# LMH6881-Breakout.net
KiCad netlist of a schematic drawn in EAGLE
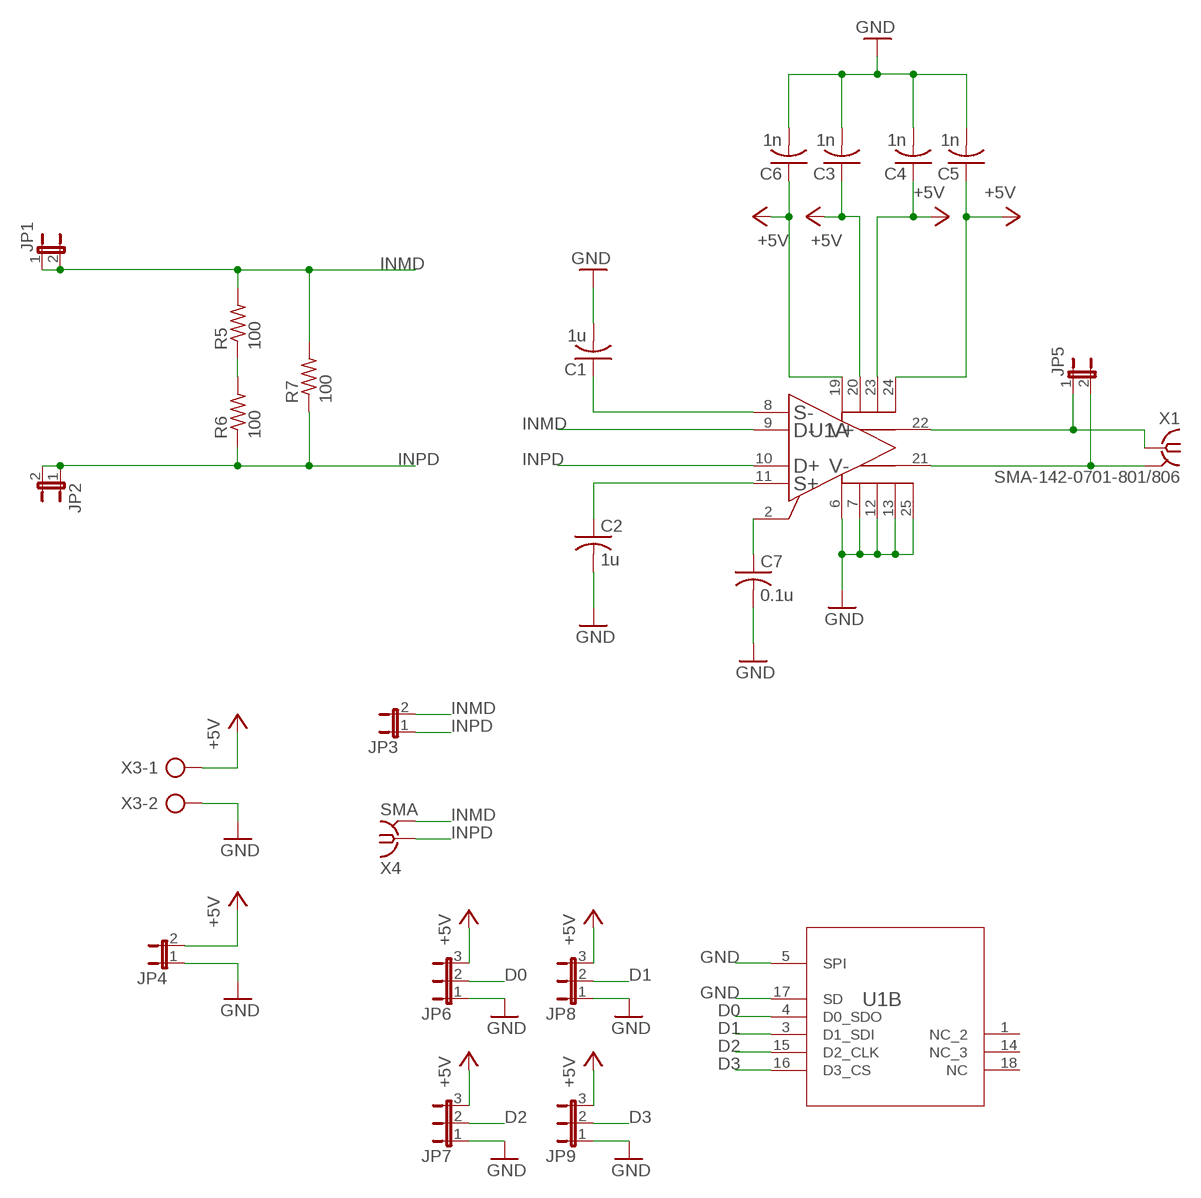
[diagram p0: schematic, sheet 1]

(export (version "E")
  (design (tool "Eeschema 10.0.6"))
  (components
    (comp (ref "C1")
      (value "1u")
      (footprint "eagle-import:C0805")
      (libsource (lib "eagle-import") (part "C-USC0805"))
    )
    (comp (ref "C2")
      (value "1u")
      (footprint "eagle-import:C0805")
      (libsource (lib "eagle-import") (part "C-USC0805"))
    )
    (comp (ref "C3")
      (value "1n")
      (footprint "eagle-import:C0805")
      (libsource (lib "eagle-import") (part "C-USC0805"))
    )
    (comp (ref "C4")
      (value "1n")
      (footprint "eagle-import:C0805")
      (libsource (lib "eagle-import") (part "C-USC0805"))
    )
    (comp (ref "C5")
      (value "1n")
      (footprint "eagle-import:C0805")
      (libsource (lib "eagle-import") (part "C-USC0805"))
    )
    (comp (ref "C6")
      (value "1n")
      (footprint "eagle-import:C0805")
      (libsource (lib "eagle-import") (part "C-USC0805"))
    )
    (comp (ref "C7")
      (value "0.1u")
      (footprint "eagle-import:C0805")
      (libsource (lib "eagle-import") (part "C-USC0805"))
    )
    (comp (ref "JP1")
      (value "JP1E")
      (footprint "eagle-import:JP1")
      (libsource (lib "eagle-import") (part "JP1E"))
    )
    (comp (ref "JP2")
      (value "JP1E")
      (footprint "eagle-import:JP1")
      (libsource (lib "eagle-import") (part "JP1E"))
    )
    (comp (ref "JP3")
      (value "JP1E")
      (footprint "eagle-import:JP1")
      (libsource (lib "eagle-import") (part "JP1E"))
    )
    (comp (ref "JP4")
      (value "JP1E")
      (footprint "eagle-import:JP1")
      (libsource (lib "eagle-import") (part "JP1E"))
    )
    (comp (ref "JP5")
      (value "JP1E")
      (footprint "eagle-import:JP1")
      (libsource (lib "eagle-import") (part "JP1E"))
    )
    (comp (ref "JP6")
      (value "JP2E")
      (footprint "eagle-import:JP2")
      (libsource (lib "eagle-import") (part "JP2E"))
    )
    (comp (ref "JP7")
      (value "JP2E")
      (footprint "eagle-import:JP2")
      (libsource (lib "eagle-import") (part "JP2E"))
    )
    (comp (ref "JP8")
      (value "JP2E")
      (footprint "eagle-import:JP2")
      (libsource (lib "eagle-import") (part "JP2E"))
    )
    (comp (ref "JP9")
      (value "JP2E")
      (footprint "eagle-import:JP2")
      (libsource (lib "eagle-import") (part "JP2E"))
    )
    (comp (ref "R5")
      (value "100")
      (footprint "eagle-import:R0805")
      (libsource (lib "eagle-import") (part "R-US_R0805"))
    )
    (comp (ref "R6")
      (value "100")
      (footprint "eagle-import:R0805")
      (libsource (lib "eagle-import") (part "R-US_R0805"))
    )
    (comp (ref "R7")
      (value "100")
      (footprint "eagle-import:R0805")
      (libsource (lib "eagle-import") (part "R-US_R0805"))
    )
    (comp (ref "U1")
      (value "LMH6881SQX/NOPB")
      (footprint "eagle-import:RTW0024A")
      (fields
        (field (name "ALTERNATEPARTNUMBER") "LMH6881SQNOPB")
        (field (name "MANUFACTURER") "Texas Instruments")
        (field (name "PARTNUMBER") "LMH6881SQXNOPB")
      )
      (libsource (lib "eagle-import") (part "LMH6881SQX/NOPB"))
    )
    (comp (ref "X1")
      (value "SMA-142-0701-801/806")
      (footprint "eagle-import:J502-ND-142-0701-801_806")
      (fields (field (name "MF") "JOHNSON COMPONENTS") (field (name "MPN") "142-0701-801"))
      (libsource (lib "eagle-import") (part "SMA-142-0701-801/806"))
    )
    (comp (ref "X3")
      (value "AK500/2")
      (footprint "eagle-import:AK500_2")
      (libsource (lib "eagle-import") (part "AK500/2"))
    )
    (comp (ref "X4")
      (value "SMA")
      (footprint "eagle-import:J502-ND-142-0701-801_806")
      (fields (field (name "MF") "JOHNSON COMPONENTS") (field (name "MPN") "142-0701-801"))
      (libsource (lib "eagle-import") (part "SMA-142-0701-801/806"))
    )
  )
  (nets
    (net (code "1") (name "+5V") (class "Default")
      (node (ref "C3") (pin "1") (pinfunction "1_1") (pintype "passive"))
      (node (ref "C4") (pin "1") (pinfunction "1_1") (pintype "passive"))
      (node (ref "C5") (pin "1") (pinfunction "1_1") (pintype "passive"))
      (node (ref "C6") (pin "1") (pinfunction "1_1") (pintype "passive"))
      (node (ref "JP4") (pin "2") (pinfunction "2_2") (pintype "passive"))
      (node (ref "JP6") (pin "3") (pinfunction "3_3") (pintype "passive"))
      (node (ref "JP7") (pin "3") (pinfunction "3_3") (pintype "passive"))
      (node (ref "JP8") (pin "3") (pinfunction "3_3") (pintype "passive"))
      (node (ref "JP9") (pin "3") (pinfunction "3_3") (pintype "passive"))
      (node (ref "U1") (pin "19") (pinfunction "VCC_2_19") (pintype "power_in"))
      (node (ref "U1") (pin "20") (pinfunction "VCC_3_20") (pintype "power_in"))
      (node (ref "U1") (pin "23") (pinfunction "VCC_4_23") (pintype "power_in"))
      (node (ref "U1") (pin "24") (pinfunction "VCC_24") (pintype "passive"))
      (node (ref "X3") (pin "1") (pinfunction "KL_1") (pintype "passive"))
    )
    (net (code "2") (name "/D0") (class "Default")
      (node (ref "JP6") (pin "2") (pinfunction "2_2") (pintype "passive"))
      (node (ref "U1") (pin "4") (pinfunction "D0_SDO_4") (pintype "bidirectional"))
    )
    (net (code "3") (name "/D1") (class "Default")
      (node (ref "JP8") (pin "2") (pinfunction "2_2") (pintype "passive"))
      (node (ref "U1") (pin "3") (pinfunction "D1_SDI_3") (pintype "input"))
    )
    (net (code "4") (name "/D2") (class "Default")
      (node (ref "JP7") (pin "2") (pinfunction "2_2") (pintype "passive"))
      (node (ref "U1") (pin "15") (pinfunction "D2_CLK_15") (pintype "input"))
    )
    (net (code "5") (name "/D3") (class "Default")
      (node (ref "JP9") (pin "2") (pinfunction "2_2") (pintype "passive"))
      (node (ref "U1") (pin "16") (pinfunction "D3_CS_16") (pintype "input"))
    )
    (net (code "6") (name "/INMD") (class "Default")
      (node (ref "JP1") (pin "1") (pinfunction "1_1") (pintype "passive"))
      (node (ref "JP1") (pin "2") (pinfunction "2_2") (pintype "passive"))
      (node (ref "JP3") (pin "2") (pinfunction "2_2") (pintype "passive"))
      (node (ref "R5") (pin "2") (pinfunction "2_2") (pintype "passive"))
      (node (ref "R7") (pin "2") (pinfunction "2_2") (pintype "passive"))
      (node (ref "U1") (pin "9") (pinfunction "INMD_9") (pintype "input"))
      (node (ref "X4") (pin "G@1") (pinfunction "2_G@1") (pintype "passive"))
      (node (ref "X4") (pin "G@2") (pinfunction "2_G@2") (pintype "passive"))
      (node (ref "X4") (pin "G@3") (pinfunction "2_G@3") (pintype "passive"))
      (node (ref "X4") (pin "G@4") (pinfunction "2_G@4") (pintype "passive"))
    )
    (net (code "7") (name "/INPD") (class "Default")
      (node (ref "JP2") (pin "1") (pinfunction "1_1") (pintype "passive"))
      (node (ref "JP2") (pin "2") (pinfunction "2_2") (pintype "passive"))
      (node (ref "JP3") (pin "1") (pinfunction "1_1") (pintype "passive"))
      (node (ref "R6") (pin "1") (pinfunction "1_1") (pintype "passive"))
      (node (ref "R7") (pin "1") (pinfunction "1_1") (pintype "passive"))
      (node (ref "U1") (pin "10") (pinfunction "INPD_10") (pintype "input"))
      (node (ref "X4") (pin "1") (pinfunction "1_1") (pintype "passive"))
    )
    (net (code "8") (name "GND") (class "Default")
      (node (ref "C1") (pin "2") (pinfunction "2_2") (pintype "passive"))
      (node (ref "C2") (pin "2") (pinfunction "2_2") (pintype "passive"))
      (node (ref "C3") (pin "2") (pinfunction "2_2") (pintype "passive"))
      (node (ref "C4") (pin "2") (pinfunction "2_2") (pintype "passive"))
      (node (ref "C5") (pin "2") (pinfunction "2_2") (pintype "passive"))
      (node (ref "C6") (pin "2") (pinfunction "2_2") (pintype "passive"))
      (node (ref "C7") (pin "2") (pinfunction "2_2") (pintype "passive"))
      (node (ref "JP4") (pin "1") (pinfunction "1_1") (pintype "passive"))
      (node (ref "JP6") (pin "1") (pinfunction "1_1") (pintype "passive"))
      (node (ref "JP7") (pin "1") (pinfunction "1_1") (pintype "passive"))
      (node (ref "JP8") (pin "1") (pinfunction "1_1") (pintype "passive"))
      (node (ref "JP9") (pin "1") (pinfunction "1_1") (pintype "passive"))
      (node (ref "U1") (pin "12") (pinfunction "GND_4_12") (pintype "power_in"))
      (node (ref "U1") (pin "13") (pinfunction "GND_13") (pintype "power_in"))
      (node (ref "U1") (pin "17") (pinfunction "SD_17") (pintype "input"))
      (node (ref "U1") (pin "25") (pinfunction "PAD_25") (pintype "passive"))
      (node (ref "U1") (pin "5") (pinfunction "SPI_5") (pintype "input"))
      (node (ref "U1") (pin "6") (pinfunction "GND_2_6") (pintype "power_in"))
      (node (ref "U1") (pin "7") (pinfunction "GND_3_7") (pintype "power_in"))
      (node (ref "X3") (pin "2") (pinfunction "KL_2") (pintype "passive"))
    )
    (net (code "9") (name "Net-(R5-Pad1)") (class "Default")
      (node (ref "R5") (pin "1") (pinfunction "1_1") (pintype "passive"))
      (node (ref "R6") (pin "2") (pinfunction "2_2") (pintype "passive"))
    )
    (net (code "10") (name "Net-(U1A-INMS)") (class "Default")
      (node (ref "C1") (pin "1") (pinfunction "1_1") (pintype "passive"))
      (node (ref "U1") (pin "8") (pinfunction "INMS_8") (pintype "input"))
    )
    (net (code "11") (name "Net-(U1A-INPS)") (class "Default")
      (node (ref "C2") (pin "1") (pinfunction "1_1") (pintype "passive"))
      (node (ref "U1") (pin "11") (pinfunction "INPS_11") (pintype "input"))
    )
    (net (code "12") (name "Net-(U1A-OCM)") (class "Default")
      (node (ref "C7") (pin "1") (pinfunction "1_1") (pintype "passive"))
      (node (ref "U1") (pin "2") (pinfunction "OCM_2") (pintype "output"))
    )
    (net (code "13") (name "Net-(U1A-OUTM)") (class "Default")
      (node (ref "JP5") (pin "2") (pinfunction "2_2") (pintype "passive"))
      (node (ref "U1") (pin "21") (pinfunction "OUTM_21") (pintype "output"))
      (node (ref "X1") (pin "G@1") (pinfunction "2_G@1") (pintype "passive"))
      (node (ref "X1") (pin "G@2") (pinfunction "2_G@2") (pintype "passive"))
      (node (ref "X1") (pin "G@3") (pinfunction "2_G@3") (pintype "passive"))
      (node (ref "X1") (pin "G@4") (pinfunction "2_G@4") (pintype "passive"))
    )
    (net (code "14") (name "Net-(U1A-OUTP)") (class "Default")
      (node (ref "JP5") (pin "1") (pinfunction "1_1") (pintype "passive"))
      (node (ref "U1") (pin "22") (pinfunction "OUTP_22") (pintype "output"))
      (node (ref "X1") (pin "1") (pinfunction "1_1") (pintype "passive"))
    )
    (net (code "15") (name "unconnected-(U1B-NC-Pad18)") (class "Default")
      (node (ref "U1") (pin "18") (pinfunction "NC_18") (pintype "passive"))
    )
    (net (code "16") (name "unconnected-(U1B-NC_2-Pad1)") (class "Default")
      (node (ref "U1") (pin "1") (pinfunction "NC_2_1") (pintype "passive"))
    )
    (net (code "17") (name "unconnected-(U1B-NC_3-Pad14)") (class "Default")
      (node (ref "U1") (pin "14") (pinfunction "NC_3_14") (pintype "passive"))
    )
  )
)
